# c122-adsr.net
KiCad netlist of a schematic drawn in EAGLE
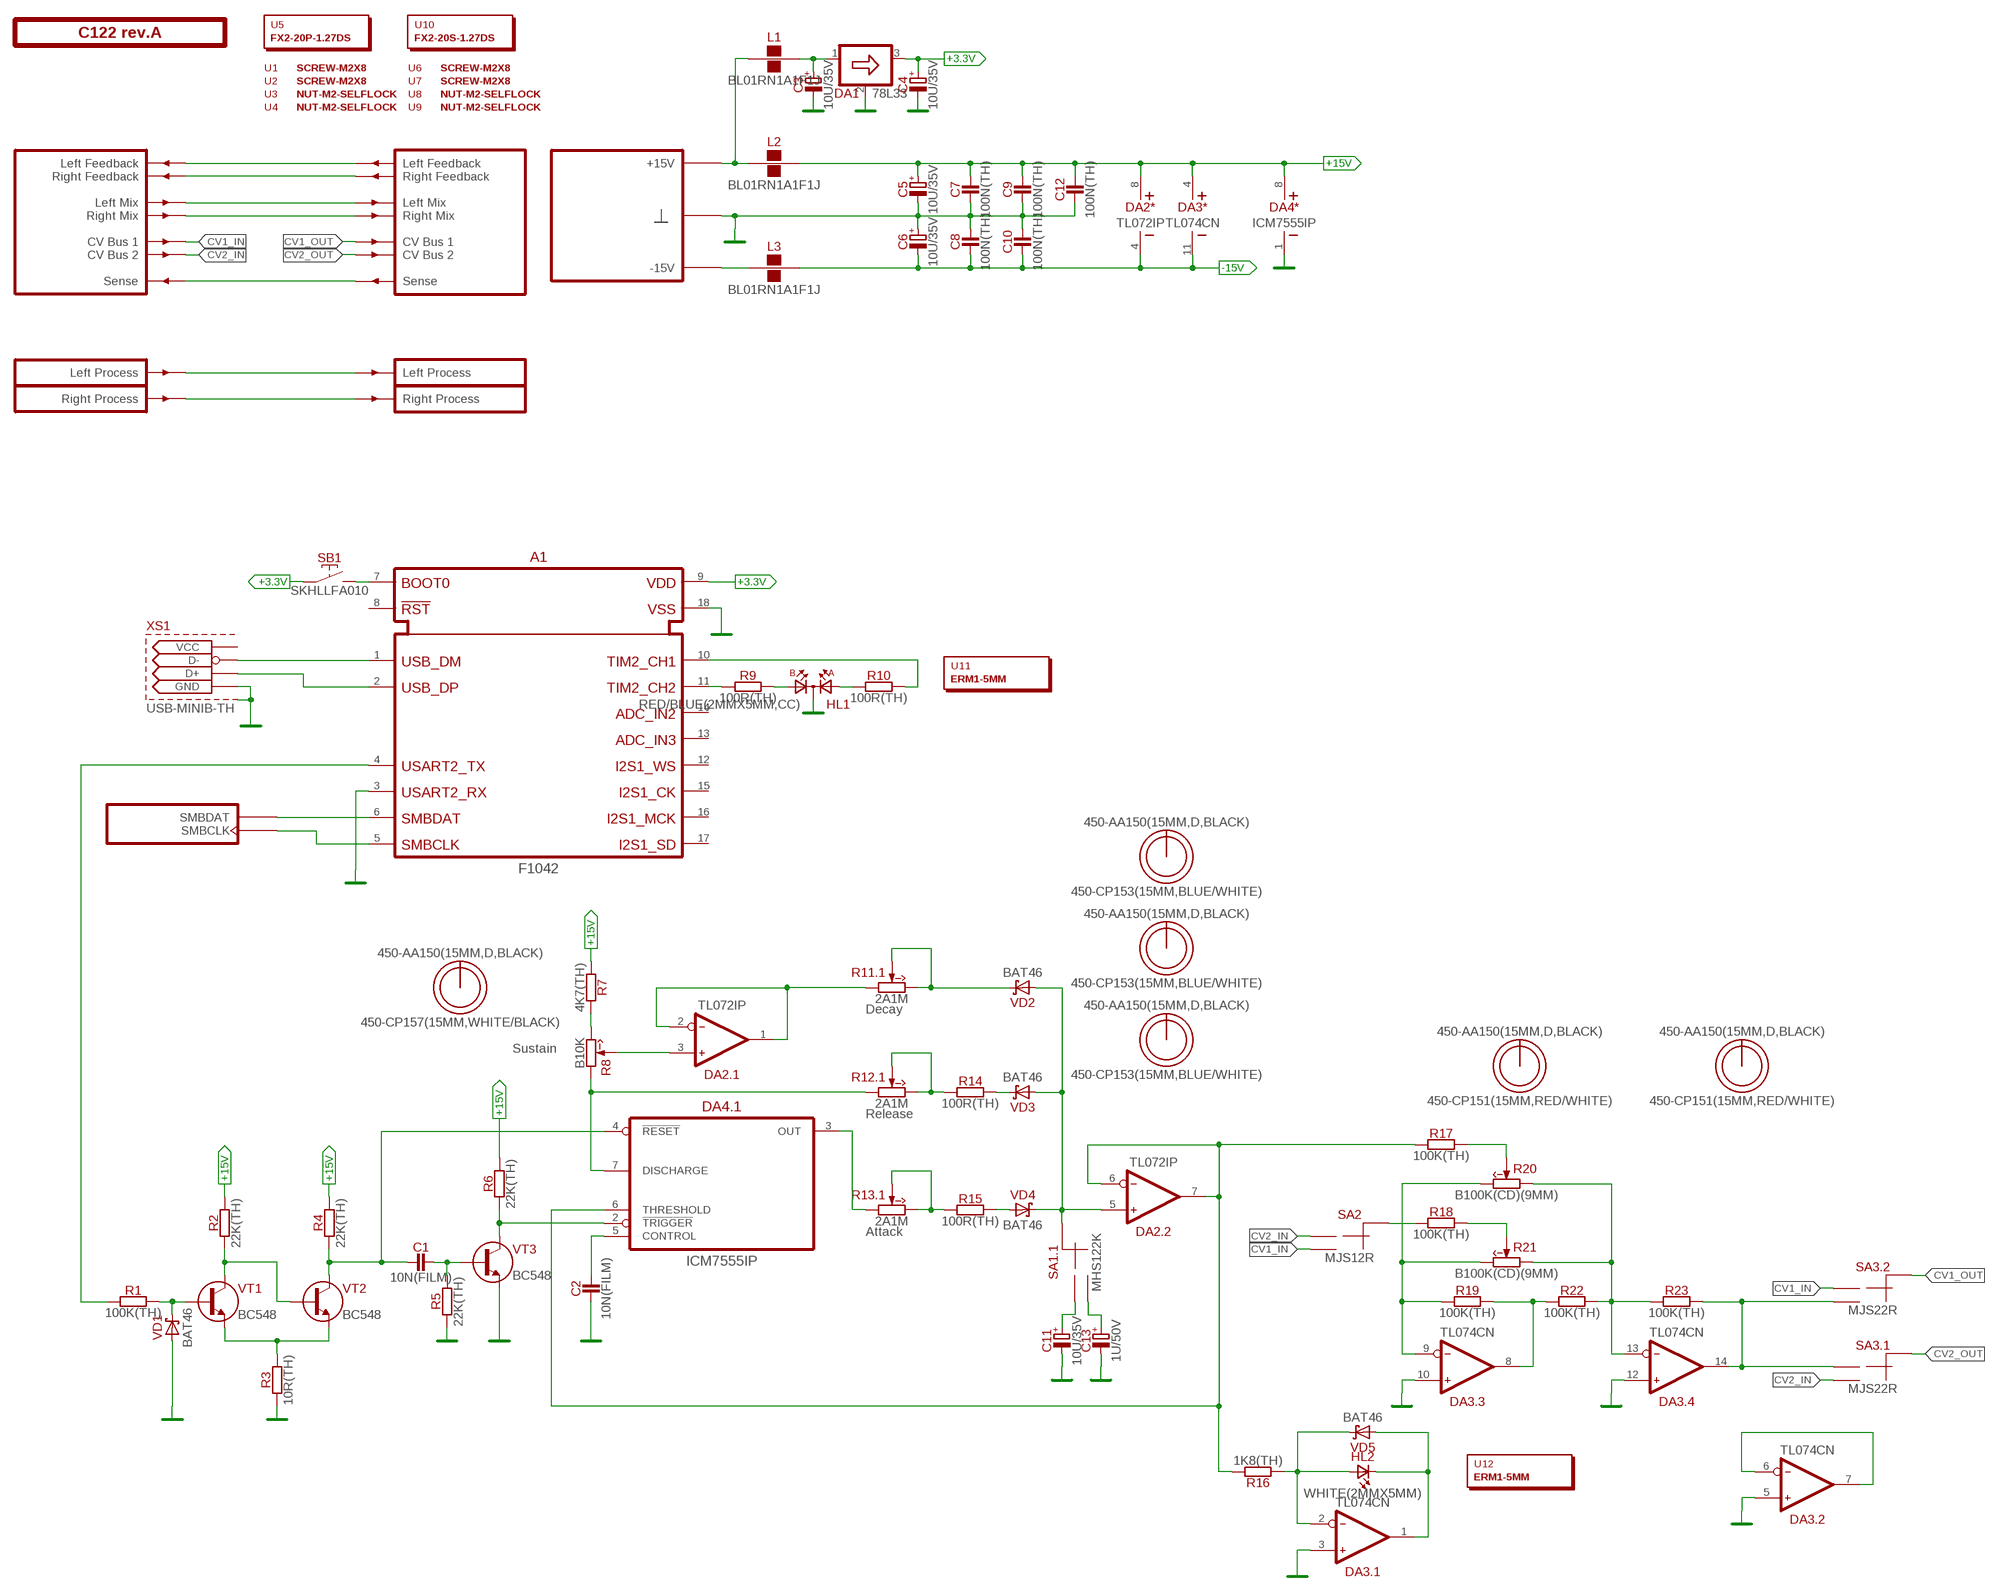
[diagram p0: schematic, sheet 1]

(export (version "E")
  (design (tool "Eeschema 10.0.6"))
  (components
    (comp (ref "A1")
      (value "F1042")
      (footprint "eagle-import:F-DIP18")
      (libsource (lib "eagle-import") (part "F1042"))
    )
    (comp (ref "C1")
      (value "10N(FILM)")
      (footprint "eagle-import:C050-025X075")
      (libsource (lib "eagle-import") (part "?10N(FILM)"))
    )
    (comp (ref "C2")
      (value "10N(FILM)")
      (footprint "eagle-import:C050-025X075")
      (libsource (lib "eagle-import") (part "?10N(FILM)"))
    )
    (comp (ref "C3")
      (value "10U/35V")
      (footprint "eagle-import:E2-5")
      (libsource (lib "eagle-import") (part "?10U/35V"))
    )
    (comp (ref "C4")
      (value "10U/35V")
      (footprint "eagle-import:E2-5")
      (libsource (lib "eagle-import") (part "?10U/35V"))
    )
    (comp (ref "C5")
      (value "10U/35V")
      (footprint "eagle-import:E2-5")
      (libsource (lib "eagle-import") (part "?10U/35V"))
    )
    (comp (ref "C6")
      (value "10U/35V")
      (footprint "eagle-import:E2-5")
      (libsource (lib "eagle-import") (part "?10U/35V"))
    )
    (comp (ref "C7")
      (value "100N(TH)")
      (footprint "eagle-import:C050-024X044")
      (libsource (lib "eagle-import") (part "?100N(TH)"))
    )
    (comp (ref "C8")
      (value "100N(TH)")
      (footprint "eagle-import:C050-024X044")
      (libsource (lib "eagle-import") (part "?100N(TH)"))
    )
    (comp (ref "C9")
      (value "100N(TH)")
      (footprint "eagle-import:C050-024X044")
      (libsource (lib "eagle-import") (part "?100N(TH)"))
    )
    (comp (ref "C10")
      (value "100N(TH)")
      (footprint "eagle-import:C050-024X044")
      (libsource (lib "eagle-import") (part "?100N(TH)"))
    )
    (comp (ref "C11")
      (value "10U/35V")
      (footprint "eagle-import:E2-5")
      (libsource (lib "eagle-import") (part "?10U/35V"))
    )
    (comp (ref "C12")
      (value "100N(TH)")
      (footprint "eagle-import:C050-024X044")
      (libsource (lib "eagle-import") (part "?100N(TH)"))
    )
    (comp (ref "C13")
      (value "1U/50V")
      (footprint "eagle-import:E1,5-4")
      (libsource (lib "eagle-import") (part "?1U/50V"))
    )
    (comp (ref "DA1")
      (value "78L33")
      (footprint "eagle-import:TO92")
      (libsource (lib "eagle-import") (part "78L33"))
    )
    (comp (ref "DA2")
      (value "TL072IP")
      (footprint "eagle-import:DIP-8")
      (libsource (lib "eagle-import") (part "TL072IP"))
    )
    (comp (ref "DA3")
      (value "TL074CN")
      (footprint "eagle-import:DIP-14")
      (libsource (lib "eagle-import") (part "TL074CN"))
    )
    (comp (ref "DA4")
      (value "ICM7555IP")
      (footprint "eagle-import:DIP-8")
      (libsource (lib "eagle-import") (part "ICM7555?IP"))
    )
    (comp (ref "HL1")
      (value "RED/BLUE(2MMX5MM,CC)")
      (footprint "eagle-import:LED2X5-3PIN")
      (libsource (lib "eagle-import") (part "?(2MMX5MM,CC)RED/BLUE"))
    )
    (comp (ref "HL2")
      (value "WHITE(2MMX5MM)")
      (footprint "eagle-import:LED2X5")
      (libsource (lib "eagle-import") (part "?(2MMX5MM)WHITE"))
    )
    (comp (ref "L1")
      (value "BL01RN1A1F1J")
      (footprint "eagle-import:BL01RN1A")
      (libsource (lib "eagle-import") (part "BL01RN1A?1F1J"))
    )
    (comp (ref "L2")
      (value "BL01RN1A1F1J")
      (footprint "eagle-import:BL01RN1A")
      (libsource (lib "eagle-import") (part "BL01RN1A?1F1J"))
    )
    (comp (ref "L3")
      (value "BL01RN1A1F1J")
      (footprint "eagle-import:BL01RN1A")
      (libsource (lib "eagle-import") (part "BL01RN1A?1F1J"))
    )
    (comp (ref "O1")
      (value "450-AA150(15MM,D,BLACK)")
      (footprint "eagle-import:EMPTY")
      (libsource (lib "eagle-import") (part "450-AA?150(15MM,D,BLACK)"))
    )
    (comp (ref "O2")
      (value "450-CP157(15MM,WHITE/BLACK)")
      (footprint "eagle-import:EMPTY")
      (libsource (lib "eagle-import") (part "450-C?P157(15MM,WHITE/BLACK)"))
    )
    (comp (ref "O3")
      (value "450-AA150(15MM,D,BLACK)")
      (footprint "eagle-import:EMPTY")
      (libsource (lib "eagle-import") (part "450-AA?150(15MM,D,BLACK)"))
    )
    (comp (ref "O4")
      (value "450-CP153(15MM,BLUE/WHITE)")
      (footprint "eagle-import:EMPTY")
      (libsource (lib "eagle-import") (part "450-C?P153(15MM,BLUE/WHITE)"))
    )
    (comp (ref "O5")
      (value "450-AA150(15MM,D,BLACK)")
      (footprint "eagle-import:EMPTY")
      (libsource (lib "eagle-import") (part "450-AA?150(15MM,D,BLACK)"))
    )
    (comp (ref "O6")
      (value "450-CP153(15MM,BLUE/WHITE)")
      (footprint "eagle-import:EMPTY")
      (libsource (lib "eagle-import") (part "450-C?P153(15MM,BLUE/WHITE)"))
    )
    (comp (ref "O7")
      (value "450-AA150(15MM,D,BLACK)")
      (footprint "eagle-import:EMPTY")
      (libsource (lib "eagle-import") (part "450-AA?150(15MM,D,BLACK)"))
    )
    (comp (ref "O8")
      (value "450-CP153(15MM,BLUE/WHITE)")
      (footprint "eagle-import:EMPTY")
      (libsource (lib "eagle-import") (part "450-C?P153(15MM,BLUE/WHITE)"))
    )
    (comp (ref "O9")
      (value "450-AA150(15MM,D,BLACK)")
      (footprint "eagle-import:EMPTY")
      (libsource (lib "eagle-import") (part "450-AA?150(15MM,D,BLACK)"))
    )
    (comp (ref "O10")
      (value "450-CP151(15MM,RED/WHITE)")
      (footprint "eagle-import:EMPTY")
      (libsource (lib "eagle-import") (part "450-C?P151(15MM,RED/WHITE)"))
    )
    (comp (ref "O11")
      (value "450-AA150(15MM,D,BLACK)")
      (footprint "eagle-import:EMPTY")
      (libsource (lib "eagle-import") (part "450-AA?150(15MM,D,BLACK)"))
    )
    (comp (ref "O12")
      (value "450-CP151(15MM,RED/WHITE)")
      (footprint "eagle-import:EMPTY")
      (libsource (lib "eagle-import") (part "450-C?P151(15MM,RED/WHITE)"))
    )
    (comp (ref "PCB1")
      (value "C122 rev.A")
      (footprint "eagle-import:ST2-BOARD-74")
      (libsource (lib "eagle-import") (part "ST2-BOARD-?74"))
    )
    (comp (ref "R1")
      (value "100K(TH)")
      (footprint "eagle-import:R-0207_10")
      (libsource (lib "eagle-import") (part "?100K(TH)"))
    )
    (comp (ref "R2")
      (value "22K(TH)")
      (footprint "eagle-import:R-0207_10")
      (libsource (lib "eagle-import") (part "?22K(TH)"))
    )
    (comp (ref "R3")
      (value "10R(TH)")
      (footprint "eagle-import:R-0207_10")
      (libsource (lib "eagle-import") (part "?10R(TH)"))
    )
    (comp (ref "R4")
      (value "22K(TH)")
      (footprint "eagle-import:R-0207_10")
      (libsource (lib "eagle-import") (part "?22K(TH)"))
    )
    (comp (ref "R5")
      (value "22K(TH)")
      (footprint "eagle-import:R-0207_10")
      (libsource (lib "eagle-import") (part "?22K(TH)"))
    )
    (comp (ref "R6")
      (value "22K(TH)")
      (footprint "eagle-import:R-0207_10")
      (libsource (lib "eagle-import") (part "?22K(TH)"))
    )
    (comp (ref "R7")
      (value "4K7(TH)")
      (footprint "eagle-import:R-0207_10")
      (libsource (lib "eagle-import") (part "?4K7(TH)"))
    )
    (comp (ref "R8")
      (value "B10K")
      (footprint "eagle-import:RV11-SINGLE")
      (libsource (lib "eagle-import") (part "?B10K"))
    )
    (comp (ref "R9")
      (value "100R(TH)")
      (footprint "eagle-import:R-0207_10")
      (libsource (lib "eagle-import") (part "?100R(TH)"))
    )
    (comp (ref "R10")
      (value "100R(TH)")
      (footprint "eagle-import:R-0207_10")
      (libsource (lib "eagle-import") (part "?100R(TH)"))
    )
    (comp (ref "R11")
      (value "2A1M")
      (footprint "eagle-import:RV11-DUAL")
      (libsource (lib "eagle-import") (part "2?A1M"))
    )
    (comp (ref "R12")
      (value "2A1M")
      (footprint "eagle-import:RV11-DUAL")
      (libsource (lib "eagle-import") (part "2?A1M"))
    )
    (comp (ref "R13")
      (value "2A1M")
      (footprint "eagle-import:RV11-DUAL")
      (libsource (lib "eagle-import") (part "2?A1M"))
    )
    (comp (ref "R14")
      (value "100R(TH)")
      (footprint "eagle-import:R-0207_10")
      (libsource (lib "eagle-import") (part "?100R(TH)"))
    )
    (comp (ref "R15")
      (value "100R(TH)")
      (footprint "eagle-import:R-0207_10")
      (libsource (lib "eagle-import") (part "?100R(TH)"))
    )
    (comp (ref "R16")
      (value "1K8(TH)")
      (footprint "eagle-import:R-0207_10")
      (libsource (lib "eagle-import") (part "?1K8(TH)"))
    )
    (comp (ref "R17")
      (value "100K(TH)")
      (footprint "eagle-import:R-0207_10")
      (libsource (lib "eagle-import") (part "?100K(TH)"))
    )
    (comp (ref "R18")
      (value "100K(TH)")
      (footprint "eagle-import:R-0207_10")
      (libsource (lib "eagle-import") (part "?100K(TH)"))
    )
    (comp (ref "R19")
      (value "100K(TH)")
      (footprint "eagle-import:R-0207_10")
      (libsource (lib "eagle-import") (part "?100K(TH)"))
    )
    (comp (ref "R20")
      (value "B100K(CD)(9MM)")
      (footprint "eagle-import:RV09-SINGLE")
      (libsource (lib "eagle-import") (part "?B100K(CD)(9MM)"))
    )
    (comp (ref "R21")
      (value "B100K(CD)(9MM)")
      (footprint "eagle-import:RV09-SINGLE")
      (libsource (lib "eagle-import") (part "?B100K(CD)(9MM)"))
    )
    (comp (ref "R22")
      (value "100K(TH)")
      (footprint "eagle-import:R-0207_10")
      (libsource (lib "eagle-import") (part "?100K(TH)"))
    )
    (comp (ref "R23")
      (value "100K(TH)")
      (footprint "eagle-import:R-0207_10")
      (libsource (lib "eagle-import") (part "?100K(TH)"))
    )
    (comp (ref "SA1")
      (value "MHS122K")
      (footprint "eagle-import:APEM-MHS122K")
      (libsource (lib "eagle-import") (part "MHS122K"))
    )
    (comp (ref "SA2")
      (value "MJS12R")
      (footprint "eagle-import:APEM-MJS12R")
      (libsource (lib "eagle-import") (part "MJS12R"))
    )
    (comp (ref "SA3")
      (value "MJS22R")
      (footprint "eagle-import:APEM-MJS22R")
      (libsource (lib "eagle-import") (part "MJS22R"))
    )
    (comp (ref "SB1")
      (value "SKHLLFA010")
      (footprint "eagle-import:SKHLLFA010")
      (libsource (lib "eagle-import") (part "SKHLLFA010"))
    )
    (comp (ref "U1")
      (value "SCREW-M2X8")
      (footprint "eagle-import:EMPTY")
      (libsource (lib "eagle-import") (part "?SCREW-M2X8"))
    )
    (comp (ref "U2")
      (value "SCREW-M2X8")
      (footprint "eagle-import:EMPTY")
      (libsource (lib "eagle-import") (part "?SCREW-M2X8"))
    )
    (comp (ref "U3")
      (value "NUT-M2-SELFLOCK")
      (footprint "eagle-import:EMPTY")
      (libsource (lib "eagle-import") (part "?NUT-M2-SELFLOCK"))
    )
    (comp (ref "U4")
      (value "NUT-M2-SELFLOCK")
      (footprint "eagle-import:EMPTY")
      (libsource (lib "eagle-import") (part "?NUT-M2-SELFLOCK"))
    )
    (comp (ref "U5")
      (value "FX2-20P-1.27DS")
      (footprint "eagle-import:EMPTY")
      (libsource (lib "eagle-import") (part "?FX2-20P-1.27DS"))
    )
    (comp (ref "U6")
      (value "SCREW-M2X8")
      (footprint "eagle-import:EMPTY")
      (libsource (lib "eagle-import") (part "?SCREW-M2X8"))
    )
    (comp (ref "U7")
      (value "SCREW-M2X8")
      (footprint "eagle-import:EMPTY")
      (libsource (lib "eagle-import") (part "?SCREW-M2X8"))
    )
    (comp (ref "U8")
      (value "NUT-M2-SELFLOCK")
      (footprint "eagle-import:EMPTY")
      (libsource (lib "eagle-import") (part "?NUT-M2-SELFLOCK"))
    )
    (comp (ref "U9")
      (value "NUT-M2-SELFLOCK")
      (footprint "eagle-import:EMPTY")
      (libsource (lib "eagle-import") (part "?NUT-M2-SELFLOCK"))
    )
    (comp (ref "U10")
      (value "FX2-20S-1.27DS")
      (footprint "eagle-import:EMPTY")
      (libsource (lib "eagle-import") (part "?FX2-20S-1.27DS"))
    )
    (comp (ref "U11")
      (value "ERM1-5MM")
      (footprint "eagle-import:EMPTY")
      (libsource (lib "eagle-import") (part "?ERM1-5MM"))
    )
    (comp (ref "U12")
      (value "ERM1-5MM")
      (footprint "eagle-import:EMPTY")
      (libsource (lib "eagle-import") (part "?ERM1-5MM"))
    )
    (comp (ref "VD1")
      (value "BAT46")
      (footprint "eagle-import:DO35-7")
      (libsource (lib "eagle-import") (part "?BAT46"))
    )
    (comp (ref "VD2")
      (value "BAT46")
      (footprint "eagle-import:DO35-7")
      (libsource (lib "eagle-import") (part "?BAT46"))
    )
    (comp (ref "VD3")
      (value "BAT46")
      (footprint "eagle-import:DO35-7")
      (libsource (lib "eagle-import") (part "?BAT46"))
    )
    (comp (ref "VD4")
      (value "BAT46")
      (footprint "eagle-import:DO35-7")
      (libsource (lib "eagle-import") (part "?BAT46"))
    )
    (comp (ref "VD5")
      (value "BAT46")
      (footprint "eagle-import:DO35-7")
      (libsource (lib "eagle-import") (part "?BAT46"))
    )
    (comp (ref "VT1")
      (value "BC548")
      (footprint "eagle-import:TO92")
      (libsource (lib "eagle-import") (part "?BC548"))
    )
    (comp (ref "VT2")
      (value "BC548")
      (footprint "eagle-import:TO92")
      (libsource (lib "eagle-import") (part "?BC548"))
    )
    (comp (ref "VT3")
      (value "BC548")
      (footprint "eagle-import:TO92")
      (libsource (lib "eagle-import") (part "?BC548"))
    )
    (comp (ref "XS1")
      (value "USB-MINIB-TH")
      (footprint "eagle-import:USB-MB-H")
      (libsource (lib "eagle-import") (part "USB-MINIB-TH"))
    )
  )
  (nets
    (net (code "1") (name "+3.3V") (class "Default")
      (node (ref "A1") (pin "9") (pinfunction "VDD_9") (pintype "input"))
      (node (ref "C4") (pin "+") (pinfunction "+_+") (pintype "passive"))
      (node (ref "DA1") (pin "3") (pinfunction "OUT_3") (pintype "power_in"))
      (node (ref "SB1") (pin "1") (pinfunction "1_1") (pintype "passive"))
    )
    (net (code "2") (name "+15V") (class "Default")
      (node (ref "C12") (pin "2") (pinfunction "2_2") (pintype "passive"))
      (node (ref "C5") (pin "+") (pinfunction "+_+") (pintype "passive"))
      (node (ref "C7") (pin "2") (pinfunction "2_2") (pintype "passive"))
      (node (ref "C9") (pin "2") (pinfunction "2_2") (pintype "passive"))
      (node (ref "DA2") (pin "8") (pinfunction "V+_8") (pintype "power_in"))
      (node (ref "DA3") (pin "4") (pinfunction "V+_4") (pintype "power_in"))
      (node (ref "DA4") (pin "8") (pinfunction "V+_8") (pintype "power_in"))
      (node (ref "L2") (pin "2") (pinfunction "2_2") (pintype "passive"))
      (node (ref "R2") (pin "2") (pinfunction "2_2") (pintype "passive"))
      (node (ref "R4") (pin "2") (pinfunction "2_2") (pintype "passive"))
      (node (ref "R6") (pin "2") (pinfunction "2_2") (pintype "passive"))
      (node (ref "R7") (pin "2") (pinfunction "2_2") (pintype "passive"))
    )
    (net (code "3") (name "-15V") (class "Default")
      (node (ref "C10") (pin "1") (pinfunction "1_1") (pintype "passive"))
      (node (ref "C6") (pin "-") (pinfunction "-_-") (pintype "passive"))
      (node (ref "C8") (pin "1") (pinfunction "1_1") (pintype "passive"))
      (node (ref "DA2") (pin "4") (pinfunction "V-_4") (pintype "power_in"))
      (node (ref "DA3") (pin "11") (pinfunction "V-_11") (pintype "power_in"))
      (node (ref "L3") (pin "2") (pinfunction "2_2") (pintype "passive"))
    )
    (net (code "4") (name "CV1_IN") (class "Default")
      (node (ref "PCB1") (pin "ACV1") (pinfunction "CV1_ACV1") (pintype "bidirectional"))
      (node (ref "SA2") (pin "NO") (pinfunction "2_NO") (pintype "passive"))
      (node (ref "SA3") (pin "NC2") (pinfunction "1_NC2") (pintype "passive"))
    )
    (net (code "5") (name "CV1_OUT") (class "Default")
      (node (ref "PCB1") (pin "ACV1'") (pinfunction "CV1'_ACV1'") (pintype "bidirectional"))
      (node (ref "SA3") (pin "C2") (pinfunction "CM_C2") (pintype "passive"))
    )
    (net (code "6") (name "CV2_IN") (class "Default")
      (node (ref "PCB1") (pin "ACV2") (pinfunction "CV2_ACV2") (pintype "bidirectional"))
      (node (ref "SA2") (pin "NC") (pinfunction "1_NC") (pintype "passive"))
      (node (ref "SA3") (pin "NO1") (pinfunction "2_NO1") (pintype "passive"))
    )
    (net (code "7") (name "CV2_OUT") (class "Default")
      (node (ref "PCB1") (pin "ACV2'") (pinfunction "CV2'_ACV2'") (pintype "bidirectional"))
      (node (ref "SA3") (pin "C1") (pinfunction "CM_C1") (pintype "passive"))
    )
    (net (code "8") (name "GND") (class "Default")
      (node (ref "A1") (pin "18") (pinfunction "VSS_18") (pintype "input"))
      (node (ref "A1") (pin "3") (pinfunction "USART2_RX_3") (pintype "input"))
      (node (ref "C10") (pin "2") (pinfunction "2_2") (pintype "passive"))
      (node (ref "C11") (pin "-") (pinfunction "-_-") (pintype "passive"))
      (node (ref "C12") (pin "1") (pinfunction "1_1") (pintype "passive"))
      (node (ref "C13") (pin "-") (pinfunction "-_-") (pintype "passive"))
      (node (ref "C2") (pin "1") (pinfunction "1_1") (pintype "passive"))
      (node (ref "C3") (pin "-") (pinfunction "-_-") (pintype "passive"))
      (node (ref "C4") (pin "-") (pinfunction "-_-") (pintype "passive"))
      (node (ref "C5") (pin "-") (pinfunction "-_-") (pintype "passive"))
      (node (ref "C6") (pin "+") (pinfunction "+_+") (pintype "passive"))
      (node (ref "C7") (pin "1") (pinfunction "1_1") (pintype "passive"))
      (node (ref "C8") (pin "2") (pinfunction "2_2") (pintype "passive"))
      (node (ref "C9") (pin "1") (pinfunction "1_1") (pintype "passive"))
      (node (ref "DA1") (pin "2") (pinfunction "GND_2") (pintype "power_in"))
      (node (ref "DA3") (pin "10") (pinfunction "IN+_10") (pintype "input"))
      (node (ref "DA3") (pin "12") (pinfunction "IN+_12") (pintype "input"))
      (node (ref "DA3") (pin "3") (pinfunction "IN+_3") (pintype "input"))
      (node (ref "DA3") (pin "5") (pinfunction "IN+_5") (pintype "input"))
      (node (ref "DA4") (pin "1") (pinfunction "V-_1") (pintype "power_in"))
      (node (ref "HL1") (pin "K") (pinfunction "K_K") (pintype "passive"))
      (node (ref "PCB1") (pin "B4") (pinfunction "GND_B4") (pintype "bidirectional"))
      (node (ref "PCB1") (pin "B4'") (pinfunction "GND_B4'") (pintype "bidirectional"))
      (node (ref "PCB1") (pin "B5") (pinfunction "GND_B5") (pintype "bidirectional"))
      (node (ref "PCB1") (pin "B5'") (pinfunction "GND_B5'") (pintype "bidirectional"))
      (node (ref "PCB1") (pin "B6") (pinfunction "GND_B6") (pintype "bidirectional"))
      (node (ref "PCB1") (pin "B6'") (pinfunction "GND_B6'") (pintype "bidirectional"))
      (node (ref "PCB1") (pin "B7") (pinfunction "GND_B7") (pintype "bidirectional"))
      (node (ref "PCB1") (pin "B7'") (pinfunction "GND_B7'") (pintype "bidirectional"))
      (node (ref "PCB1") (pin "B8") (pinfunction "GND_B8") (pintype "bidirectional"))
      (node (ref "PCB1") (pin "B8'") (pinfunction "GND_B8'") (pintype "bidirectional"))
      (node (ref "R3") (pin "1") (pinfunction "1_1") (pintype "passive"))
      (node (ref "R5") (pin "1") (pinfunction "1_1") (pintype "passive"))
      (node (ref "VD1") (pin "A") (pinfunction "A_A") (pintype "passive"))
      (node (ref "VT3") (pin "3") (pinfunction "E_3") (pintype "passive"))
      (node (ref "XS1") (pin "GND") (pinfunction "GND_GND") (pintype "passive"))
      (node (ref "XS1") (pin "P$1") (pinfunction "S1_P$1") (pintype "passive"))
      (node (ref "XS1") (pin "P$2") (pinfunction "S1_P$2") (pintype "passive"))
      (node (ref "XS1") (pin "P$6") (pinfunction "S1_P$6") (pintype "passive"))
      (node (ref "XS1") (pin "P$7") (pinfunction "S1_P$7") (pintype "passive"))
    )
    (net (code "9") (name "Net-(A1-BOOT0)") (class "Default")
      (node (ref "A1") (pin "7") (pinfunction "BOOT0_7") (pintype "input"))
      (node (ref "SB1") (pin "2") (pinfunction "2_2") (pintype "passive"))
    )
    (net (code "10") (name "Net-(A1-SBMDAT)") (class "Default")
      (node (ref "A1") (pin "6") (pinfunction "SBMDAT_6") (pintype "input"))
      (node (ref "PCB1") (pin "ASMBDAT") (pinfunction "SMBDAT_ASMBDAT") (pintype "bidirectional"))
      (node (ref "PCB1") (pin "ASMBDAT'") (pinfunction "SMBDAT_ASMBDAT'") (pintype "bidirectional"))
    )
    (net (code "11") (name "Net-(A1-SMBCLK)") (class "Default")
      (node (ref "A1") (pin "5") (pinfunction "SMBCLK_5") (pintype "input"))
      (node (ref "PCB1") (pin "ASMBCLK") (pinfunction "SMBCLK_ASMBCLK") (pintype "bidirectional"))
      (node (ref "PCB1") (pin "ASMBCLK'") (pinfunction "SMBCLK_ASMBCLK'") (pintype "bidirectional"))
    )
    (net (code "12") (name "Net-(A1-TIM2_CH1)") (class "Default")
      (node (ref "A1") (pin "10") (pinfunction "TIM2_CH1_10") (pintype "input"))
      (node (ref "R10") (pin "2") (pinfunction "2_2") (pintype "passive"))
    )
    (net (code "13") (name "Net-(A1-TIM2_CH2)") (class "Default")
      (node (ref "A1") (pin "11") (pinfunction "TIM2_CH2_11") (pintype "input"))
      (node (ref "R9") (pin "1") (pinfunction "1_1") (pintype "passive"))
    )
    (net (code "14") (name "Net-(A1-USART2_TX)") (class "Default")
      (node (ref "A1") (pin "4") (pinfunction "USART2_TX_4") (pintype "input"))
      (node (ref "R1") (pin "1") (pinfunction "1_1") (pintype "passive"))
    )
    (net (code "15") (name "Net-(A1-USB_DM)") (class "Default")
      (node (ref "A1") (pin "1") (pinfunction "USB_DM_1") (pintype "input"))
      (node (ref "XS1") (pin "D-") (pinfunction "D-_D-") (pintype "bidirectional"))
    )
    (net (code "16") (name "Net-(A1-USB_DP)") (class "Default")
      (node (ref "A1") (pin "2") (pinfunction "USB_DP_2") (pintype "input"))
      (node (ref "XS1") (pin "D+") (pinfunction "D+_D+") (pintype "bidirectional"))
    )
    (net (code "17") (name "Net-(C11-Pad+)") (class "Default")
      (node (ref "C11") (pin "+") (pinfunction "+_+") (pintype "passive"))
      (node (ref "SA1") (pin "1") (pinfunction "1_1") (pintype "passive"))
    )
    (net (code "18") (name "Net-(C13-Pad+)") (class "Default")
      (node (ref "C13") (pin "+") (pinfunction "+_+") (pintype "passive"))
      (node (ref "SA1") (pin "2") (pinfunction "2_2") (pintype "passive"))
    )
    (net (code "19") (name "Net-(DA1-IN)") (class "Default")
      (node (ref "C3") (pin "+") (pinfunction "+_+") (pintype "passive"))
      (node (ref "DA1") (pin "1") (pinfunction "IN_1") (pintype "power_in"))
      (node (ref "L1") (pin "2") (pinfunction "2_2") (pintype "passive"))
    )
    (net (code "20") (name "Net-(DA2B-IN+)") (class "Default")
      (node (ref "DA2") (pin "3") (pinfunction "IN+_3") (pintype "input"))
      (node (ref "R8") (pin "2") (pinfunction "W_2") (pintype "passive"))
    )
    (net (code "21") (name "Net-(DA2B-IN-)") (class "Default")
      (node (ref "DA2") (pin "1") (pinfunction "OUT_1") (pintype "output"))
      (node (ref "DA2") (pin "2") (pinfunction "IN-_2") (pintype "input"))
      (node (ref "R11") (pin "1") (pinfunction "CCW_1") (pintype "passive"))
    )
    (net (code "22") (name "Net-(DA2C-IN+)") (class "Default")
      (node (ref "DA2") (pin "5") (pinfunction "IN+_5") (pintype "input"))
      (node (ref "SA1") (pin "CMN") (pinfunction "CM_CMN") (pintype "passive"))
      (node (ref "VD2") (pin "A") (pinfunction "A_A") (pintype "passive"))
      (node (ref "VD3") (pin "A") (pinfunction "A_A") (pintype "passive"))
      (node (ref "VD4") (pin "C") (pinfunction "C_C") (pintype "passive"))
    )
    (net (code "23") (name "Net-(DA2C-IN-)") (class "Default")
      (node (ref "DA2") (pin "6") (pinfunction "IN-_6") (pintype "input"))
      (node (ref "DA2") (pin "7") (pinfunction "OUT_7") (pintype "output"))
      (node (ref "DA4") (pin "6") (pinfunction "THRESHOLD_6") (pintype "bidirectional"))
      (node (ref "R16") (pin "2") (pinfunction "2_2") (pintype "passive"))
      (node (ref "R17") (pin "1") (pinfunction "1_1") (pintype "passive"))
    )
    (net (code "24") (name "Net-(DA3B-IN-)") (class "Default")
      (node (ref "DA3") (pin "2") (pinfunction "IN-_2") (pintype "input"))
      (node (ref "HL2") (pin "A") (pinfunction "A_A") (pintype "passive"))
      (node (ref "R16") (pin "1") (pinfunction "1_1") (pintype "passive"))
      (node (ref "VD5") (pin "C") (pinfunction "C_C") (pintype "passive"))
    )
    (net (code "25") (name "Net-(DA3B-OUT)") (class "Default")
      (node (ref "DA3") (pin "1") (pinfunction "OUT_1") (pintype "output"))
      (node (ref "HL2") (pin "K") (pinfunction "C_K") (pintype "passive"))
      (node (ref "VD5") (pin "A") (pinfunction "A_A") (pintype "passive"))
    )
    (net (code "26") (name "Net-(DA3C-IN-)") (class "Default")
      (node (ref "DA3") (pin "6") (pinfunction "IN-_6") (pintype "input"))
      (node (ref "DA3") (pin "7") (pinfunction "OUT_7") (pintype "output"))
    )
    (net (code "27") (name "Net-(DA3D-IN-)") (class "Default")
      (node (ref "DA3") (pin "9") (pinfunction "IN-_9") (pintype "input"))
      (node (ref "R19") (pin "1") (pinfunction "1_1") (pintype "passive"))
      (node (ref "R20") (pin "3") (pinfunction "CW_3") (pintype "passive"))
      (node (ref "R21") (pin "3") (pinfunction "CW_3") (pintype "passive"))
    )
    (net (code "28") (name "Net-(DA3D-OUT)") (class "Default")
      (node (ref "DA3") (pin "8") (pinfunction "OUT_8") (pintype "output"))
      (node (ref "R19") (pin "2") (pinfunction "2_2") (pintype "passive"))
      (node (ref "R22") (pin "1") (pinfunction "1_1") (pintype "passive"))
    )
    (net (code "29") (name "Net-(DA3E-IN-)") (class "Default")
      (node (ref "DA3") (pin "13") (pinfunction "IN-_13") (pintype "input"))
      (node (ref "R20") (pin "1") (pinfunction "CCW_1") (pintype "passive"))
      (node (ref "R21") (pin "1") (pinfunction "CCW_1") (pintype "passive"))
      (node (ref "R22") (pin "2") (pinfunction "2_2") (pintype "passive"))
      (node (ref "R23") (pin "1") (pinfunction "1_1") (pintype "passive"))
    )
    (net (code "30") (name "Net-(DA3E-OUT)") (class "Default")
      (node (ref "DA3") (pin "14") (pinfunction "OUT_14") (pintype "output"))
      (node (ref "R23") (pin "2") (pinfunction "2_2") (pintype "passive"))
      (node (ref "SA3") (pin "NC1") (pinfunction "1_NC1") (pintype "passive"))
      (node (ref "SA3") (pin "NO2") (pinfunction "2_NO2") (pintype "passive"))
    )
    (net (code "31") (name "Net-(DA4B-CONTROL)") (class "Default")
      (node (ref "C2") (pin "2") (pinfunction "2_2") (pintype "passive"))
      (node (ref "DA4") (pin "5") (pinfunction "CONTROL_5") (pintype "bidirectional"))
    )
    (net (code "32") (name "Net-(DA4B-DISCHARGE)") (class "Default")
      (node (ref "DA4") (pin "7") (pinfunction "DISCHARGE_7") (pintype "bidirectional"))
      (node (ref "R12") (pin "1") (pinfunction "CCW_1") (pintype "passive"))
      (node (ref "R8") (pin "1") (pinfunction "CCW_1") (pintype "passive"))
    )
    (net (code "33") (name "Net-(DA4B-OUT)") (class "Default")
      (node (ref "DA4") (pin "3") (pinfunction "OUT_3") (pintype "bidirectional"))
      (node (ref "R13") (pin "1") (pinfunction "CCW_1") (pintype "passive"))
    )
    (net (code "34") (name "Net-(DA4B-~{RESET})") (class "Default")
      (node (ref "C1") (pin "1") (pinfunction "1_1") (pintype "passive"))
      (node (ref "DA4") (pin "4") (pinfunction "~{RESET}_4") (pintype "input"))
      (node (ref "R4") (pin "1") (pinfunction "1_1") (pintype "passive"))
      (node (ref "VT2") (pin "1") (pinfunction "C_1") (pintype "passive"))
    )
    (net (code "35") (name "Net-(DA4B-~{TRIGGER})") (class "Default")
      (node (ref "DA4") (pin "2") (pinfunction "~{TRIGGER}_2") (pintype "bidirectional"))
      (node (ref "R6") (pin "1") (pinfunction "1_1") (pintype "passive"))
      (node (ref "VT3") (pin "1") (pinfunction "C_1") (pintype "passive"))
    )
    (net (code "36") (name "Net-(HL1-PadA1)") (class "Default")
      (node (ref "HL1") (pin "A1") (pinfunction "A1_A1") (pintype "passive"))
      (node (ref "R10") (pin "1") (pinfunction "1_1") (pintype "passive"))
    )
    (net (code "37") (name "Net-(HL1-PadA2)") (class "Default")
      (node (ref "HL1") (pin "A2") (pinfunction "A2_A2") (pintype "passive"))
      (node (ref "R9") (pin "2") (pinfunction "2_2") (pintype "passive"))
    )
    (net (code "38") (name "Net-(L1-Pad1)") (class "Default")
      (node (ref "L1") (pin "1") (pinfunction "1_1") (pintype "passive"))
      (node (ref "L2") (pin "1") (pinfunction "1_1") (pintype "passive"))
      (node (ref "PCB1") (pin "A+15") (pinfunction "P+15V_A+15") (pintype "bidirectional"))
      (node (ref "PCB1") (pin "A+15'") (pinfunction "P+15V_A+15'") (pintype "bidirectional"))
      (node (ref "PCB1") (pin "B+15") (pinfunction "P+15V_B+15") (pintype "bidirectional"))
      (node (ref "PCB1") (pin "B+15'") (pinfunction "P+15V_B+15'") (pintype "bidirectional"))
    )
    (net (code "39") (name "Net-(L3-Pad1)") (class "Default")
      (node (ref "L3") (pin "1") (pinfunction "1_1") (pintype "passive"))
      (node (ref "PCB1") (pin "A-15") (pinfunction "P-15V_A-15") (pintype "bidirectional"))
      (node (ref "PCB1") (pin "A-15'") (pinfunction "P-15V_A-15'") (pintype "bidirectional"))
      (node (ref "PCB1") (pin "B-15") (pinfunction "P-15V_B-15") (pintype "bidirectional"))
      (node (ref "PCB1") (pin "B-15'") (pinfunction "P-15V_B-15'") (pintype "bidirectional"))
    )
    (net (code "40") (name "Net-(PCB1B-INL)") (class "Default")
      (node (ref "PCB1") (pin "BINL") (pinfunction "INL_BINL") (pintype "bidirectional"))
      (node (ref "PCB1") (pin "BOUTL'") (pinfunction "OUTL_BOUTL'") (pintype "bidirectional"))
    )
    (net (code "41") (name "Net-(PCB1C-INR)") (class "Default")
      (node (ref "PCB1") (pin "BINR") (pinfunction "INR_BINR") (pintype "bidirectional"))
      (node (ref "PCB1") (pin "BOUTR'") (pinfunction "OUTR_BOUTR'") (pintype "bidirectional"))
    )
    (net (code "42") (name "Net-(PCB1F-LFBK)") (class "Default")
      (node (ref "PCB1") (pin "ALFBK") (pinfunction "LFBK_ALFBK") (pintype "bidirectional"))
      (node (ref "PCB1") (pin "ALFBK'") (pinfunction "LFBK'_ALFBK'") (pintype "bidirectional"))
    )
    (net (code "43") (name "Net-(PCB1F-LMIX)") (class "Default")
      (node (ref "PCB1") (pin "ALMIX") (pinfunction "LMIX_ALMIX") (pintype "bidirectional"))
      (node (ref "PCB1") (pin "ALMIX'") (pinfunction "LMIX'_ALMIX'") (pintype "bidirectional"))
    )
    (net (code "44") (name "Net-(PCB1F-RFBK)") (class "Default")
      (node (ref "PCB1") (pin "ARFBK") (pinfunction "RFBK_ARFBK") (pintype "bidirectional"))
      (node (ref "PCB1") (pin "ARFBK'") (pinfunction "RFBK'_ARFBK'") (pintype "bidirectional"))
    )
    (net (code "45") (name "Net-(PCB1F-RMIX)") (class "Default")
      (node (ref "PCB1") (pin "ARMIX") (pinfunction "RMIX_ARMIX") (pintype "bidirectional"))
      (node (ref "PCB1") (pin "ARMIX'") (pinfunction "RMIX'_ARMIX'") (pintype "bidirectional"))
    )
    (net (code "46") (name "Net-(PCB1F-SENSE)") (class "Default")
      (node (ref "PCB1") (pin "BSENSE") (pinfunction "SENSE_BSENSE") (pintype "bidirectional"))
      (node (ref "PCB1") (pin "BSENSE'") (pinfunction "SENSE'_BSENSE'") (pintype "bidirectional"))
    )
    (net (code "47") (name "Net-(R8-CW)") (class "Default")
      (node (ref "R7") (pin "1") (pinfunction "1_1") (pintype "passive"))
      (node (ref "R8") (pin "3") (pinfunction "CW_3") (pintype "passive"))
    )
    (net (code "48") (name "Net-(R11A-CW)") (class "Default")
      (node (ref "R11") (pin "2") (pinfunction "W_2") (pintype "passive"))
      (node (ref "R11") (pin "3") (pinfunction "CW_3") (pintype "passive"))
      (node (ref "VD2") (pin "C") (pinfunction "C_C") (pintype "passive"))
    )
    (net (code "49") (name "Net-(R12A-CW)") (class "Default")
      (node (ref "R12") (pin "2") (pinfunction "W_2") (pintype "passive"))
      (node (ref "R12") (pin "3") (pinfunction "CW_3") (pintype "passive"))
      (node (ref "R14") (pin "1") (pinfunction "1_1") (pintype "passive"))
    )
    (net (code "50") (name "Net-(R13A-CW)") (class "Default")
      (node (ref "R13") (pin "2") (pinfunction "W_2") (pintype "passive"))
      (node (ref "R13") (pin "3") (pinfunction "CW_3") (pintype "passive"))
      (node (ref "R15") (pin "1") (pinfunction "1_1") (pintype "passive"))
    )
    (net (code "51") (name "Net-(R14-Pad2)") (class "Default")
      (node (ref "R14") (pin "2") (pinfunction "2_2") (pintype "passive"))
      (node (ref "VD3") (pin "C") (pinfunction "C_C") (pintype "passive"))
    )
    (net (code "52") (name "Net-(R15-Pad2)") (class "Default")
      (node (ref "R15") (pin "2") (pinfunction "2_2") (pintype "passive"))
      (node (ref "VD4") (pin "A") (pinfunction "A_A") (pintype "passive"))
    )
    (net (code "53") (name "Net-(R20-W)") (class "Default")
      (node (ref "R17") (pin "2") (pinfunction "2_2") (pintype "passive"))
      (node (ref "R20") (pin "2") (pinfunction "W_2") (pintype "passive"))
    )
    (net (code "54") (name "Net-(R21-W)") (class "Default")
      (node (ref "R18") (pin "2") (pinfunction "2_2") (pintype "passive"))
      (node (ref "R21") (pin "2") (pinfunction "W_2") (pintype "passive"))
    )
    (net (code "55") (name "Net-(SA2-CM)") (class "Default")
      (node (ref "R18") (pin "1") (pinfunction "1_1") (pintype "passive"))
      (node (ref "SA2") (pin "C") (pinfunction "CM_C") (pintype "passive"))
    )
    (net (code "56") (name "Net-(VT1-B)") (class "Default")
      (node (ref "R1") (pin "2") (pinfunction "2_2") (pintype "passive"))
      (node (ref "VD1") (pin "C") (pinfunction "C_C") (pintype "passive"))
      (node (ref "VT1") (pin "2") (pinfunction "B_2") (pintype "passive"))
    )
    (net (code "57") (name "Net-(VT1-C)") (class "Default")
      (node (ref "R2") (pin "1") (pinfunction "1_1") (pintype "passive"))
      (node (ref "VT1") (pin "1") (pinfunction "C_1") (pintype "passive"))
      (node (ref "VT2") (pin "2") (pinfunction "B_2") (pintype "passive"))
    )
    (net (code "58") (name "Net-(VT1-E)") (class "Default")
      (node (ref "R3") (pin "2") (pinfunction "2_2") (pintype "passive"))
      (node (ref "VT1") (pin "3") (pinfunction "E_3") (pintype "passive"))
      (node (ref "VT2") (pin "3") (pinfunction "E_3") (pintype "passive"))
    )
    (net (code "59") (name "Net-(VT3-B)") (class "Default")
      (node (ref "C1") (pin "2") (pinfunction "2_2") (pintype "passive"))
      (node (ref "R5") (pin "2") (pinfunction "2_2") (pintype "passive"))
      (node (ref "VT3") (pin "2") (pinfunction "B_2") (pintype "passive"))
    )
    (net (code "60") (name "unconnected-(A1-ADC_IN2-Pad14)") (class "Default")
      (node (ref "A1") (pin "14") (pinfunction "ADC_IN2_14") (pintype "input"))
    )
    (net (code "61") (name "unconnected-(A1-ADC_IN3-Pad13)") (class "Default")
      (node (ref "A1") (pin "13") (pinfunction "ADC_IN3_13") (pintype "input"))
    )
    (net (code "62") (name "unconnected-(A1-I2S1_CK-Pad15)") (class "Default")
      (node (ref "A1") (pin "15") (pinfunction "I2S1_CK_15") (pintype "input"))
    )
    (net (code "63") (name "unconnected-(A1-I2S1_MCK-Pad16)") (class "Default")
      (node (ref "A1") (pin "16") (pinfunction "I2S1_MCK_16") (pintype "input"))
    )
    (net (code "64") (name "unconnected-(A1-I2S1_SD-Pad17)") (class "Default")
      (node (ref "A1") (pin "17") (pinfunction "I2S1_SD_17") (pintype "input"))
    )
    (net (code "65") (name "unconnected-(A1-I2S1_WS-Pad12)") (class "Default")
      (node (ref "A1") (pin "12") (pinfunction "I2S1_WS_12") (pintype "input"))
    )
    (net (code "66") (name "unconnected-(A1-~{RST}-Pad8)") (class "Default")
      (node (ref "A1") (pin "8") (pinfunction "~{RST}_8") (pintype "input"))
    )
    (net (code "67") (name "unconnected-(XS1-VCC-PadVBUS)") (class "Default")
      (node (ref "XS1") (pin "VBUS") (pinfunction "VCC_VBUS") (pintype "passive"))
    )
  )
)
